# Blinking_LED.net
KiCad netlist of a schematic drawn in Altium Designer
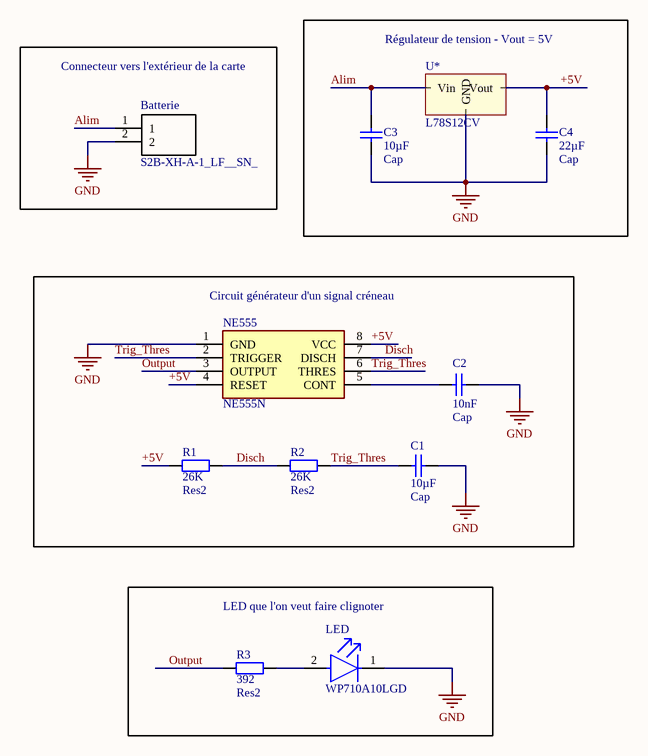
[diagram p0: Blinking_LED.SchDoc]

(export (version "E")
  (design (tool "Eeschema 10.0.6"))
  (components
    (comp (ref "Batterie")
      (value "S2B-XH-A-1_LF__SN_")
      (footprint "S2B-XH-A")
      (description "Connector")
      (fields (field (name "MANUFACTURER_PART_NUMBER") "S2B-XH-A-1(LF)(SN)"))
      (libsource (lib "SamacSys") (part "S2B-XH-A-1_LF__SN_"))
    )
    (comp (ref "C1")
      (value "Cap")
      (footprint "Capacitor 1206")
      (description "Capacitor")
      (fields (field (name "ALTIUM_VALUE") "10µF") (field (name "PUBLISHER") "Altium Limited"))
      (libsource (lib "Miscellaneous Devices") (part "Cap"))
    )
    (comp (ref "C2")
      (value "Cap")
      (footprint "Capacitor 1206")
      (description "Capacitor")
      (fields (field (name "ALTIUM_VALUE") "10nF") (field (name "PUBLISHER") "Altium Limited"))
      (libsource (lib "Miscellaneous Devices") (part "Cap"))
    )
    (comp (ref "C3")
      (value "Cap")
      (footprint "Capacitor 1206")
      (description "Capacitor")
      (fields (field (name "ALTIUM_VALUE") "10µF") (field (name "PUBLISHER") "Altium Limited"))
      (libsource (lib "Miscellaneous Devices") (part "Cap"))
    )
    (comp (ref "C4")
      (value "Cap")
      (footprint "Capacitor 1206")
      (description "Capacitor")
      (fields (field (name "ALTIUM_VALUE") "22µF") (field (name "PUBLISHER") "Altium Limited"))
      (libsource (lib "Miscellaneous Devices") (part "Cap"))
    )
    (comp (ref "LED")
      (value "WP710A10LGD")
      (footprint "FP-WP710A10LGD-MFG")
      (description "WP710A10LGD LED Thru-Hole PCB Green T-1 3mm Green Lens 2 mA 568 nm 2 mcd Round")
      (libsource (lib "Altium Content Vault") (part "8706943c75ba83719d021d2fdc84c58"))
    )
    (comp (ref "NE555")
      (value "NE555N")
      (footprint "SamacSys:DIP762W56P254L959H533Q8N")
      (description "Integrated Circuit")
      (libsource (lib "Robot_2020") (part "NE555N"))
    )
    (comp (ref "R1")
      (value "Res2")
      (footprint "Resistor 1206")
      (description "Resistor")
      (fields (field (name "ALTIUM_VALUE") "26K") (field (name "PUBLISHER") "Altium Limited"))
      (libsource (lib "Miscellaneous Devices") (part "Res2"))
    )
    (comp (ref "R2")
      (value "Res2")
      (footprint "Resistor 1206")
      (description "Resistor")
      (fields (field (name "ALTIUM_VALUE") "26K") (field (name "PUBLISHER") "Altium Limited"))
      (libsource (lib "Miscellaneous Devices") (part "Res2"))
    )
    (comp (ref "R3")
      (value "Res2")
      (footprint "Resistor 1206")
      (description "Resistor")
      (fields (field (name "ALTIUM_VALUE") "392") (field (name "PUBLISHER") "Altium Limited"))
      (libsource (lib "Miscellaneous Devices") (part "Res2"))
    )
    (comp (ref "U*")
      (value "L78S12CV")
      (footprint "R-78B")
      (libsource (lib "Robot_2020") (part "Régulateur de tension linéaire"))
    )
  )
  (nets
    (net (code "1") (name "/+5V") (class "Default")
      (node (ref "C4") (pin "2") (pinfunction "2_2") (pintype "passive"))
      (node (ref "NE555") (pin "4") (pinfunction "RESET_4") (pintype "passive"))
      (node (ref "NE555") (pin "8") (pinfunction "VCC_8") (pintype "passive"))
      (node (ref "R1") (pin "2") (pinfunction "2_2") (pintype "passive"))
      (node (ref "U*") (pin "1") (pinfunction "Vout_1") (pintype "passive"))
    )
    (net (code "2") (name "/Alim") (class "Default")
      (node (ref "Batterie") (pin "1") (pinfunction "1_1") (pintype "passive"))
      (node (ref "C3") (pin "1") (pinfunction "1_1") (pintype "passive"))
      (node (ref "U*") (pin "3") (pinfunction "Vin_3") (pintype "passive"))
    )
    (net (code "3") (name "/Disch") (class "Default")
      (node (ref "NE555") (pin "7") (pinfunction "DISCH_7") (pintype "passive"))
      (node (ref "R1") (pin "1") (pinfunction "1_1") (pintype "passive"))
      (node (ref "R2") (pin "2") (pinfunction "2_2") (pintype "passive"))
    )
    (net (code "4") (name "/Output") (class "Default")
      (node (ref "NE555") (pin "3") (pinfunction "OUTPUT_3") (pintype "passive"))
      (node (ref "R3") (pin "2") (pinfunction "2_2") (pintype "passive"))
    )
    (net (code "5") (name "/Trig_Thres") (class "Default")
      (node (ref "C1") (pin "2") (pinfunction "2_2") (pintype "passive"))
      (node (ref "NE555") (pin "2") (pinfunction "TRIGGER_2") (pintype "passive"))
      (node (ref "NE555") (pin "6") (pinfunction "THRES_6") (pintype "passive"))
      (node (ref "R2") (pin "1") (pinfunction "1_1") (pintype "passive"))
    )
    (net (code "6") (name "GND") (class "Default")
      (node (ref "Batterie") (pin "2") (pinfunction "2_2") (pintype "passive"))
      (node (ref "C1") (pin "1") (pinfunction "1_1") (pintype "passive"))
      (node (ref "C2") (pin "2") (pinfunction "2_2") (pintype "passive"))
      (node (ref "C3") (pin "2") (pinfunction "2_2") (pintype "passive"))
      (node (ref "C4") (pin "1") (pinfunction "1_1") (pintype "passive"))
      (node (ref "LED") (pin "1") (pinfunction "C_1") (pintype "passive"))
      (node (ref "NE555") (pin "1") (pinfunction "GND_1") (pintype "passive"))
      (node (ref "U*") (pin "2") (pinfunction "GND_2") (pintype "passive"))
    )
    (net (code "7") (name "Net-(LED-A)") (class "Default")
      (node (ref "LED") (pin "2") (pinfunction "A_2") (pintype "passive"))
      (node (ref "R3") (pin "1") (pinfunction "1_1") (pintype "passive"))
    )
    (net (code "8") (name "Net-(NE555-CONT)") (class "Default")
      (node (ref "C2") (pin "1") (pinfunction "1_1") (pintype "passive"))
      (node (ref "NE555") (pin "5") (pinfunction "CONT_5") (pintype "passive"))
    )
  )
)
